# OZ440-SE140-CAR001_sheet3_Power_Switch.net
KiCad netlist of a schematic drawn in Altium Designer
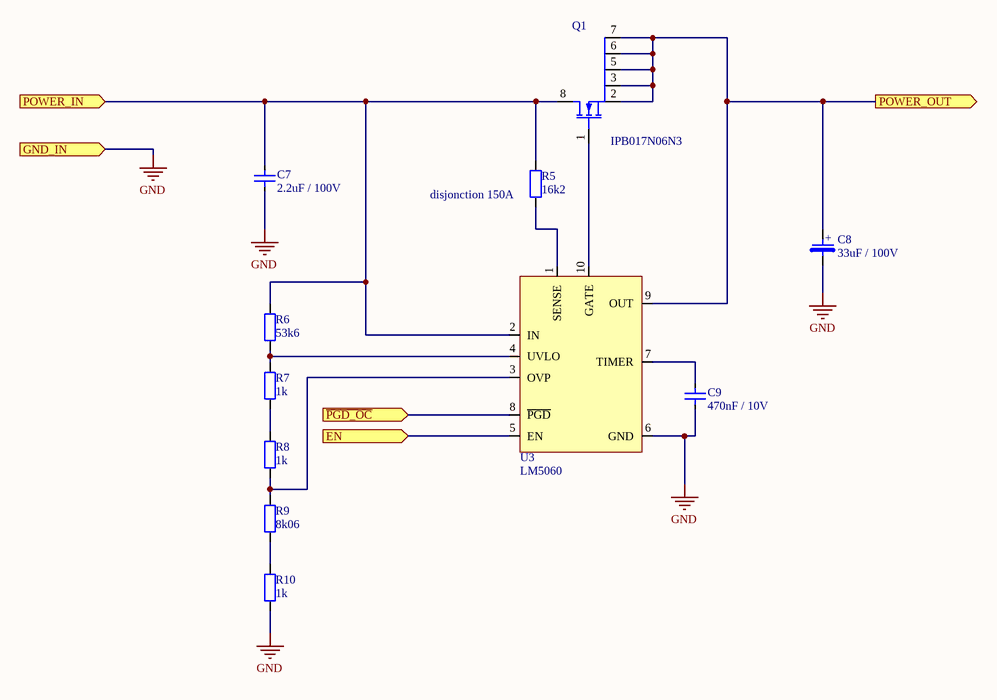
[diagram p0: OZ440-SE140-CAR001_sheet3_Power_Switch.SchDoc]

(export (version "E")
  (design (tool "Eeschema 10.0.6"))
  (components
    (comp (ref "C7")
      (value "CAP-SMD")
      (footprint "C1206-STD")
      (description "1206 2.2uF / 100V X7S ceramic capacitor")
      (fields
        (field (name "DISPLAYED REFERENCE") "2.2uF / 100V")
        (field (name "TOLERANCE") "+/- 10%")
        (field (name "MANUFACTURER") "TDK")
      )
      (libsource (lib "lib_NAIO") (part "CAP-SMD"))
    )
    (comp (ref "C8")
      (value "CAP-POL-SMD")
      (footprint "CAP-ELECTRO-SMD_SIZE_G")
      (description "33uF / 100V Aluminium capacitor SMD")
      (fields (field (name "DISPLAYED REFERENCE") "33uF / 100V") (field (name "MANUFACTURER") "Panasonic"))
      (libsource (lib "lib_NAIO") (part "CAP-POL-SMD"))
    )
    (comp (ref "C9")
      (value "CAP-SMD")
      (footprint "C0603-STD")
      (description "0603 470nF / 10V X5R ceramic capacitor")
      (fields
        (field (name "DISPLAYED REFERENCE") "470nF / 10V")
        (field (name "TOLERANCE") "+/- 10%")
        (field (name "MANUFACTURER") "AVX")
      )
      (libsource (lib "lib_NAIO") (part "CAP-SMD"))
    )
    (comp (ref "Q1")
      (value "IPB039N10N3-PGTO263_3")
      (footprint "TO263-3-SPE-IPB039N10N3")
      (description "60V/180A N channel MOSFET in DPAK package")
      (fields (field (name "DISPLAYED REFERENCE") "IPB017N06N3") (field (name "MANUFACTURER") "INFINEON"))
      (libsource (lib "lib_NAIO") (part "IPB039N10N3-PGTO263_3"))
    )
    (comp (ref "R5")
      (value "RES-SMD")
      (footprint "R0805-STD")
      (description "16k2 Ohm 0805 SMD resistor")
      (fields
        (field (name "DISPLAYED REFERENCE") "16k2")
        (field (name "TOLERANCE") "1%")
        (field (name "MANUFACTURER") "Vishay")
      )
      (libsource (lib "lib_NAIO") (part "RES-SMD"))
    )
    (comp (ref "R6")
      (value "RES-SMD")
      (footprint "R0805-STD")
      (description "53k6 Ohm 0805 SMD resistor")
      (fields
        (field (name "DISPLAYED REFERENCE") "53k6")
        (field (name "TOLERANCE") "1%")
        (field (name "MANUFACTURER") "Vishay")
      )
      (libsource (lib "lib_NAIO") (part "RES-SMD"))
    )
    (comp (ref "R7")
      (value "RES-SMD")
      (footprint "R0805-STD")
      (description "1k Ohm 0805 SMD resistor")
      (fields
        (field (name "DISPLAYED REFERENCE") "1k")
        (field (name "TOLERANCE") "1 %")
        (field (name "MANUFACTURER") "Vishay")
      )
      (libsource (lib "lib_NAIO") (part "RES-SMD"))
    )
    (comp (ref "R8")
      (value "RES-SMD")
      (footprint "R0805-STD")
      (description "1k Ohm 0805 SMD resistor")
      (fields
        (field (name "DISPLAYED REFERENCE") "1k")
        (field (name "TOLERANCE") "1 %")
        (field (name "MANUFACTURER") "Vishay")
      )
      (libsource (lib "lib_NAIO") (part "RES-SMD"))
    )
    (comp (ref "R9")
      (value "RES-SMD")
      (footprint "R0805-STD")
      (description "8k06 Ohm 0805 SMD resistor")
      (fields
        (field (name "DISPLAYED REFERENCE") "8k06")
        (field (name "TOLERANCE") "1%")
        (field (name "MANUFACTURER") "Vishay")
      )
      (libsource (lib "lib_NAIO") (part "RES-SMD"))
    )
    (comp (ref "R10")
      (value "RES-SMD")
      (footprint "R0805-STD")
      (description "1k Ohm 0805 SMD resistor")
      (fields
        (field (name "DISPLAYED REFERENCE") "1k")
        (field (name "TOLERANCE") "1 %")
        (field (name "MANUFACTURER") "Vishay")
      )
      (libsource (lib "lib_NAIO") (part "RES-SMD"))
    )
    (comp (ref "U3")
      (value "LM5060-VSSOP10")
      (footprint "VSSOP10-SPE-LM5060")
      (description "High-Side Protection Controller")
      (fields (field (name "DISPLAYED REFERENCE") "LM5060") (field (name "MANUFACTURER") "TI"))
      (libsource (lib "lib_NAIO") (part "LM5060-VSSOP10"))
    )
  )
  (nets
    (net (code "1") (name "/EN") (class "Default")
      (node (ref "U3") (pin "5") (pinfunction "EN_5") (pintype "passive"))
    )
    (net (code "2") (name "/PGD_OC") (class "Default")
      (node (ref "U3") (pin "8") (pinfunction "PGD_8") (pintype "passive"))
    )
    (net (code "3") (name "/POWER_IN") (class "Default")
      (node (ref "C7") (pin "2") (pinfunction "2_2") (pintype "passive"))
      (node (ref "Q1") (pin "8") (pinfunction "S_8") (pintype "passive"))
      (node (ref "R5") (pin "2") (pinfunction "2_2") (pintype "passive"))
      (node (ref "R6") (pin "2") (pinfunction "2_2") (pintype "passive"))
      (node (ref "U3") (pin "2") (pinfunction "IN_2") (pintype "passive"))
    )
    (net (code "4") (name "/POWER_OUT") (class "Default")
      (node (ref "C8") (pin "1") (pinfunction "1_1") (pintype "passive"))
      (node (ref "Q1") (pin "2") (pinfunction "D_2") (pintype "passive"))
      (node (ref "Q1") (pin "3") (pinfunction "D_3") (pintype "passive"))
      (node (ref "Q1") (pin "5") (pinfunction "D_5") (pintype "passive"))
      (node (ref "Q1") (pin "6") (pinfunction "D_6") (pintype "passive"))
      (node (ref "Q1") (pin "7") (pinfunction "D_7") (pintype "passive"))
      (node (ref "U3") (pin "9") (pinfunction "OUT_9") (pintype "passive"))
    )
    (net (code "5") (name "GND") (class "Default")
      (node (ref "C7") (pin "1") (pinfunction "1_1") (pintype "passive"))
      (node (ref "C8") (pin "2") (pinfunction "2_2") (pintype "passive"))
      (node (ref "C9") (pin "1") (pinfunction "1_1") (pintype "passive"))
      (node (ref "R10") (pin "1") (pinfunction "1_1") (pintype "passive"))
      (node (ref "U3") (pin "6") (pinfunction "GND_6") (pintype "passive"))
    )
    (net (code "6") (name "Net-(Q1-G)") (class "Default")
      (node (ref "Q1") (pin "1") (pinfunction "G_1") (pintype "passive"))
      (node (ref "U3") (pin "10") (pinfunction "GATE_10") (pintype "passive"))
    )
    (net (code "7") (name "Net-(R7-Pad1)") (class "Default")
      (node (ref "R7") (pin "1") (pinfunction "1_1") (pintype "passive"))
      (node (ref "R8") (pin "2") (pinfunction "2_2") (pintype "passive"))
    )
    (net (code "8") (name "Net-(R10-Pad2)") (class "Default")
      (node (ref "R10") (pin "2") (pinfunction "2_2") (pintype "passive"))
      (node (ref "R9") (pin "1") (pinfunction "1_1") (pintype "passive"))
    )
    (net (code "9") (name "Net-(U3-OVP)") (class "Default")
      (node (ref "R8") (pin "1") (pinfunction "1_1") (pintype "passive"))
      (node (ref "R9") (pin "2") (pinfunction "2_2") (pintype "passive"))
      (node (ref "U3") (pin "3") (pinfunction "OVP_3") (pintype "passive"))
    )
    (net (code "10") (name "Net-(U3-SENSE)") (class "Default")
      (node (ref "R5") (pin "1") (pinfunction "1_1") (pintype "passive"))
      (node (ref "U3") (pin "1") (pinfunction "SENSE_1") (pintype "passive"))
    )
    (net (code "11") (name "Net-(U3-TIMER)") (class "Default")
      (node (ref "C9") (pin "2") (pinfunction "2_2") (pintype "passive"))
      (node (ref "U3") (pin "7") (pinfunction "TIMER_7") (pintype "passive"))
    )
    (net (code "12") (name "Net-(U3-UVLO)") (class "Default")
      (node (ref "R6") (pin "1") (pinfunction "1_1") (pintype "passive"))
      (node (ref "R7") (pin "2") (pinfunction "2_2") (pintype "passive"))
      (node (ref "U3") (pin "4") (pinfunction "UVLO_4") (pintype "passive"))
    )
  )
)
